# speech1.net
KiCad netlist of a schematic drawn in EAGLE
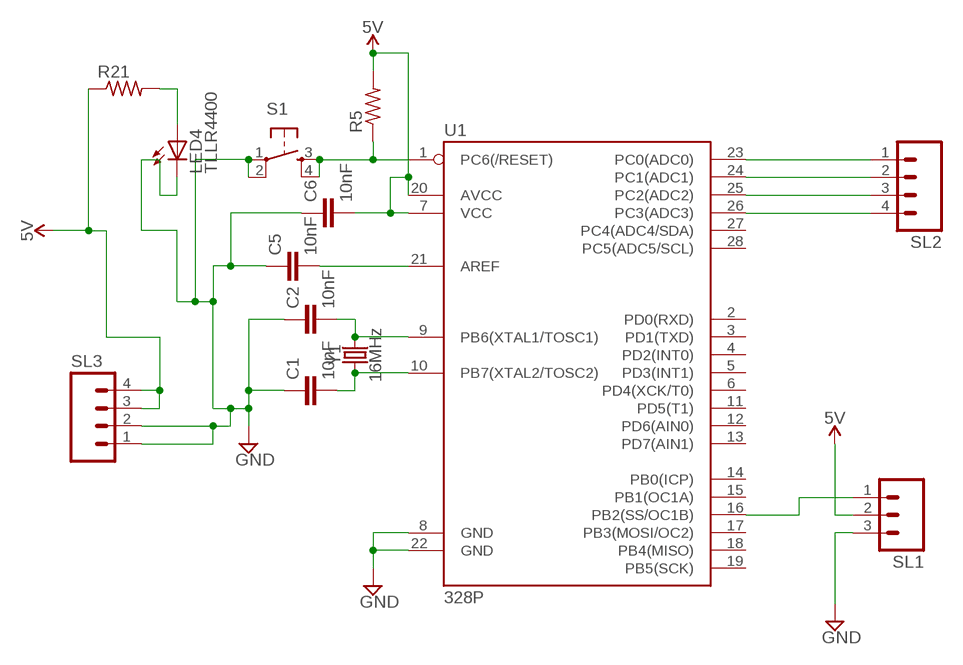
[diagram p0: schematic, sheet 1]

(export (version "E")
  (design (tool "Eeschema 10.0.6"))
  (components
    (comp (ref "C1")
      (value "10nF")
      (footprint "eagle-import:CAP-PTH-10MM")
      (libsource (lib "eagle-import") (part "10NF-PTH-10MM-10000V-1-%"))
    )
    (comp (ref "C2")
      (value "10nF")
      (footprint "eagle-import:CAP-PTH-10MM")
      (libsource (lib "eagle-import") (part "10NF-PTH-10MM-10000V-1-%"))
    )
    (comp (ref "C5")
      (value "10nF")
      (footprint "eagle-import:CAP-PTH-10MM")
      (libsource (lib "eagle-import") (part "10NF-PTH-10MM-10000V-1-%"))
    )
    (comp (ref "C6")
      (value "10nF")
      (footprint "eagle-import:CAP-PTH-10MM")
      (libsource (lib "eagle-import") (part "10NF-PTH-10MM-10000V-1-%"))
    )
    (comp (ref "LED4")
      (value "TLLR4400")
      (footprint "eagle-import:LED3MM")
      (fields (field (name "MF") "VISHAY SEMICONDUCTOR"))
      (libsource (lib "eagle-import") (part "TLLR4400"))
    )
    (comp (ref "R5")
      (value "R-US_0207/12")
      (footprint "eagle-import:0207_12")
      (libsource (lib "eagle-import") (part "R-US_0207/12"))
    )
    (comp (ref "R21")
      (value "R-US_0207/12")
      (footprint "eagle-import:0207_12")
      (libsource (lib "eagle-import") (part "R-US_0207/12"))
    )
    (comp (ref "S1")
      (value "TAC_SWITCHPTH")
      (footprint "eagle-import:TACTILE-PTH")
      (libsource (lib "eagle-import") (part "TAC_SWITCHPTH"))
    )
    (comp (ref "SL1")
      (value "MA03")
      (footprint "eagle-import:03P")
      (libsource (lib "eagle-import") (part "MA03"))
    )
    (comp (ref "SL2")
      (value "MA04")
      (footprint "eagle-import:04PA")
      (libsource (lib "eagle-import") (part "MA04"))
    )
    (comp (ref "SL3")
      (value "MA04")
      (footprint "eagle-import:04PA")
      (libsource (lib "eagle-import") (part "MA04"))
    )
    (comp (ref "U1")
      (value "328P")
      (footprint "eagle-import:DIP28")
      (libsource (lib "eagle-import") (part "ATMEGA328P_PDIP"))
    )
    (comp (ref "Y1")
      (value "16MHz")
      (footprint "eagle-import:HC49US")
      (libsource (lib "eagle-import") (part "CRYSTAL-16MHZPTH-HC49US"))
    )
  )
  (nets
    (net (code "1") (name "5V") (class "Default")
      (node (ref "C6") (pin "2") (pinfunction "2_2") (pintype "passive"))
      (node (ref "R21") (pin "1") (pinfunction "1_1") (pintype "passive"))
      (node (ref "R5") (pin "2") (pinfunction "2_2") (pintype "passive"))
      (node (ref "SL1") (pin "2") (pinfunction "2_2") (pintype "passive"))
      (node (ref "SL3") (pin "3") (pinfunction "3_3") (pintype "passive"))
      (node (ref "SL3") (pin "4") (pinfunction "4_4") (pintype "passive"))
      (node (ref "U1") (pin "20") (pinfunction "AVCC_20") (pintype "bidirectional"))
      (node (ref "U1") (pin "7") (pinfunction "VCC_7") (pintype "bidirectional"))
    )
    (net (code "2") (name "GND") (class "Default")
      (node (ref "C1") (pin "1") (pinfunction "1_1") (pintype "passive"))
      (node (ref "C2") (pin "1") (pinfunction "1_1") (pintype "passive"))
      (node (ref "C5") (pin "1") (pinfunction "1_1") (pintype "passive"))
      (node (ref "C6") (pin "1") (pinfunction "1_1") (pintype "passive"))
      (node (ref "LED4") (pin "K") (pinfunction "C_K") (pintype "passive"))
      (node (ref "S1") (pin "1") (pinfunction "1_1") (pintype "passive"))
      (node (ref "S1") (pin "2") (pinfunction "2_2") (pintype "passive"))
      (node (ref "SL1") (pin "3") (pinfunction "3_3") (pintype "passive"))
      (node (ref "SL3") (pin "1") (pinfunction "1_1") (pintype "passive"))
      (node (ref "SL3") (pin "2") (pinfunction "2_2") (pintype "passive"))
      (node (ref "U1") (pin "22") (pinfunction "GND_22") (pintype "bidirectional"))
      (node (ref "U1") (pin "8") (pinfunction "GND_8") (pintype "bidirectional"))
    )
    (net (code "3") (name "Net-(LED4-PadA)") (class "Default")
      (node (ref "LED4") (pin "A") (pinfunction "A_A") (pintype "passive"))
      (node (ref "R21") (pin "2") (pinfunction "2_2") (pintype "passive"))
    )
    (net (code "4") (name "Net-(U1-AREF)") (class "Default")
      (node (ref "C5") (pin "2") (pinfunction "2_2") (pintype "passive"))
      (node (ref "U1") (pin "21") (pinfunction "AREF_21") (pintype "bidirectional"))
    )
    (net (code "5") (name "Net-(U1-PB2(SS{slash}OC1B))") (class "Default")
      (node (ref "SL1") (pin "1") (pinfunction "1_1") (pintype "passive"))
      (node (ref "U1") (pin "16") (pinfunction "PB2(SS/OC1B)_16") (pintype "bidirectional"))
    )
    (net (code "6") (name "Net-(U1-PB6(XTAL1{slash}TOSC1))") (class "Default")
      (node (ref "C2") (pin "2") (pinfunction "2_2") (pintype "passive"))
      (node (ref "U1") (pin "9") (pinfunction "PB6(XTAL1/TOSC1)_9") (pintype "bidirectional"))
      (node (ref "Y1") (pin "2") (pinfunction "2_2") (pintype "passive"))
    )
    (net (code "7") (name "Net-(U1-PB7(XTAL2{slash}TOSC2))") (class "Default")
      (node (ref "C1") (pin "2") (pinfunction "2_2") (pintype "passive"))
      (node (ref "U1") (pin "10") (pinfunction "PB7(XTAL2/TOSC2)_10") (pintype "bidirectional"))
      (node (ref "Y1") (pin "1") (pinfunction "1_1") (pintype "passive"))
    )
    (net (code "8") (name "Net-(U1-PC0(ADC0))") (class "Default")
      (node (ref "SL2") (pin "1") (pinfunction "1_1") (pintype "passive"))
      (node (ref "U1") (pin "23") (pinfunction "PC0(ADC0)_23") (pintype "bidirectional"))
    )
    (net (code "9") (name "Net-(U1-PC1(ADC1))") (class "Default")
      (node (ref "SL2") (pin "2") (pinfunction "2_2") (pintype "passive"))
      (node (ref "U1") (pin "24") (pinfunction "PC1(ADC1)_24") (pintype "bidirectional"))
    )
    (net (code "10") (name "Net-(U1-PC2(ADC2))") (class "Default")
      (node (ref "SL2") (pin "3") (pinfunction "3_3") (pintype "passive"))
      (node (ref "U1") (pin "25") (pinfunction "PC2(ADC2)_25") (pintype "bidirectional"))
    )
    (net (code "11") (name "Net-(U1-PC3(ADC3))") (class "Default")
      (node (ref "SL2") (pin "4") (pinfunction "4_4") (pintype "passive"))
      (node (ref "U1") (pin "26") (pinfunction "PC3(ADC3)_26") (pintype "bidirectional"))
    )
    (net (code "12") (name "Net-(U1-PC6({slash}RESET))") (class "Default")
      (node (ref "R5") (pin "1") (pinfunction "1_1") (pintype "passive"))
      (node (ref "S1") (pin "3") (pinfunction "3_3") (pintype "passive"))
      (node (ref "S1") (pin "4") (pinfunction "4_4") (pintype "passive"))
      (node (ref "U1") (pin "1") (pinfunction "PC6(/RESET)_1") (pintype "bidirectional"))
    )
    (net (code "13") (name "unconnected-(U1-PB0(ICP)-Pad14)") (class "Default")
      (node (ref "U1") (pin "14") (pinfunction "PB0(ICP)_14") (pintype "bidirectional"))
    )
    (net (code "14") (name "unconnected-(U1-PB1(OC1A)-Pad15)") (class "Default")
      (node (ref "U1") (pin "15") (pinfunction "PB1(OC1A)_15") (pintype "bidirectional"))
    )
    (net (code "15") (name "unconnected-(U1-PB3(MOSI{slash}OC2)-Pad17)") (class "Default")
      (node (ref "U1") (pin "17") (pinfunction "PB3(MOSI/OC2)_17") (pintype "bidirectional"))
    )
    (net (code "16") (name "unconnected-(U1-PB4(MISO)-Pad18)") (class "Default")
      (node (ref "U1") (pin "18") (pinfunction "PB4(MISO)_18") (pintype "bidirectional"))
    )
    (net (code "17") (name "unconnected-(U1-PB5(SCK)-Pad19)") (class "Default")
      (node (ref "U1") (pin "19") (pinfunction "PB5(SCK)_19") (pintype "bidirectional"))
    )
    (net (code "18") (name "unconnected-(U1-PC4(ADC4{slash}SDA)-Pad27)") (class "Default")
      (node (ref "U1") (pin "27") (pinfunction "PC4(ADC4/SDA)_27") (pintype "bidirectional"))
    )
    (net (code "19") (name "unconnected-(U1-PC5(ADC5{slash}SCL)-Pad28)") (class "Default")
      (node (ref "U1") (pin "28") (pinfunction "PC5(ADC5/SCL)_28") (pintype "bidirectional"))
    )
    (net (code "20") (name "unconnected-(U1-PD0(RXD)-Pad2)") (class "Default")
      (node (ref "U1") (pin "2") (pinfunction "PD0(RXD)_2") (pintype "bidirectional"))
    )
    (net (code "21") (name "unconnected-(U1-PD1(TXD)-Pad3)") (class "Default")
      (node (ref "U1") (pin "3") (pinfunction "PD1(TXD)_3") (pintype "bidirectional"))
    )
    (net (code "22") (name "unconnected-(U1-PD2(INT0)-Pad4)") (class "Default")
      (node (ref "U1") (pin "4") (pinfunction "PD2(INT0)_4") (pintype "bidirectional"))
    )
    (net (code "23") (name "unconnected-(U1-PD3(INT1)-Pad5)") (class "Default")
      (node (ref "U1") (pin "5") (pinfunction "PD3(INT1)_5") (pintype "bidirectional"))
    )
    (net (code "24") (name "unconnected-(U1-PD4(XCK{slash}T0)-Pad6)") (class "Default")
      (node (ref "U1") (pin "6") (pinfunction "PD4(XCK/T0)_6") (pintype "bidirectional"))
    )
    (net (code "25") (name "unconnected-(U1-PD5(T1)-Pad11)") (class "Default")
      (node (ref "U1") (pin "11") (pinfunction "PD5(T1)_11") (pintype "bidirectional"))
    )
    (net (code "26") (name "unconnected-(U1-PD6(AIN0)-Pad12)") (class "Default")
      (node (ref "U1") (pin "12") (pinfunction "PD6(AIN0)_12") (pintype "bidirectional"))
    )
    (net (code "27") (name "unconnected-(U1-PD7(AIN1)-Pad13)") (class "Default")
      (node (ref "U1") (pin "13") (pinfunction "PD7(AIN1)_13") (pintype "bidirectional"))
    )
  )
)
